# Output13-21.net
KiCad netlist of a schematic drawn in Altium Designer
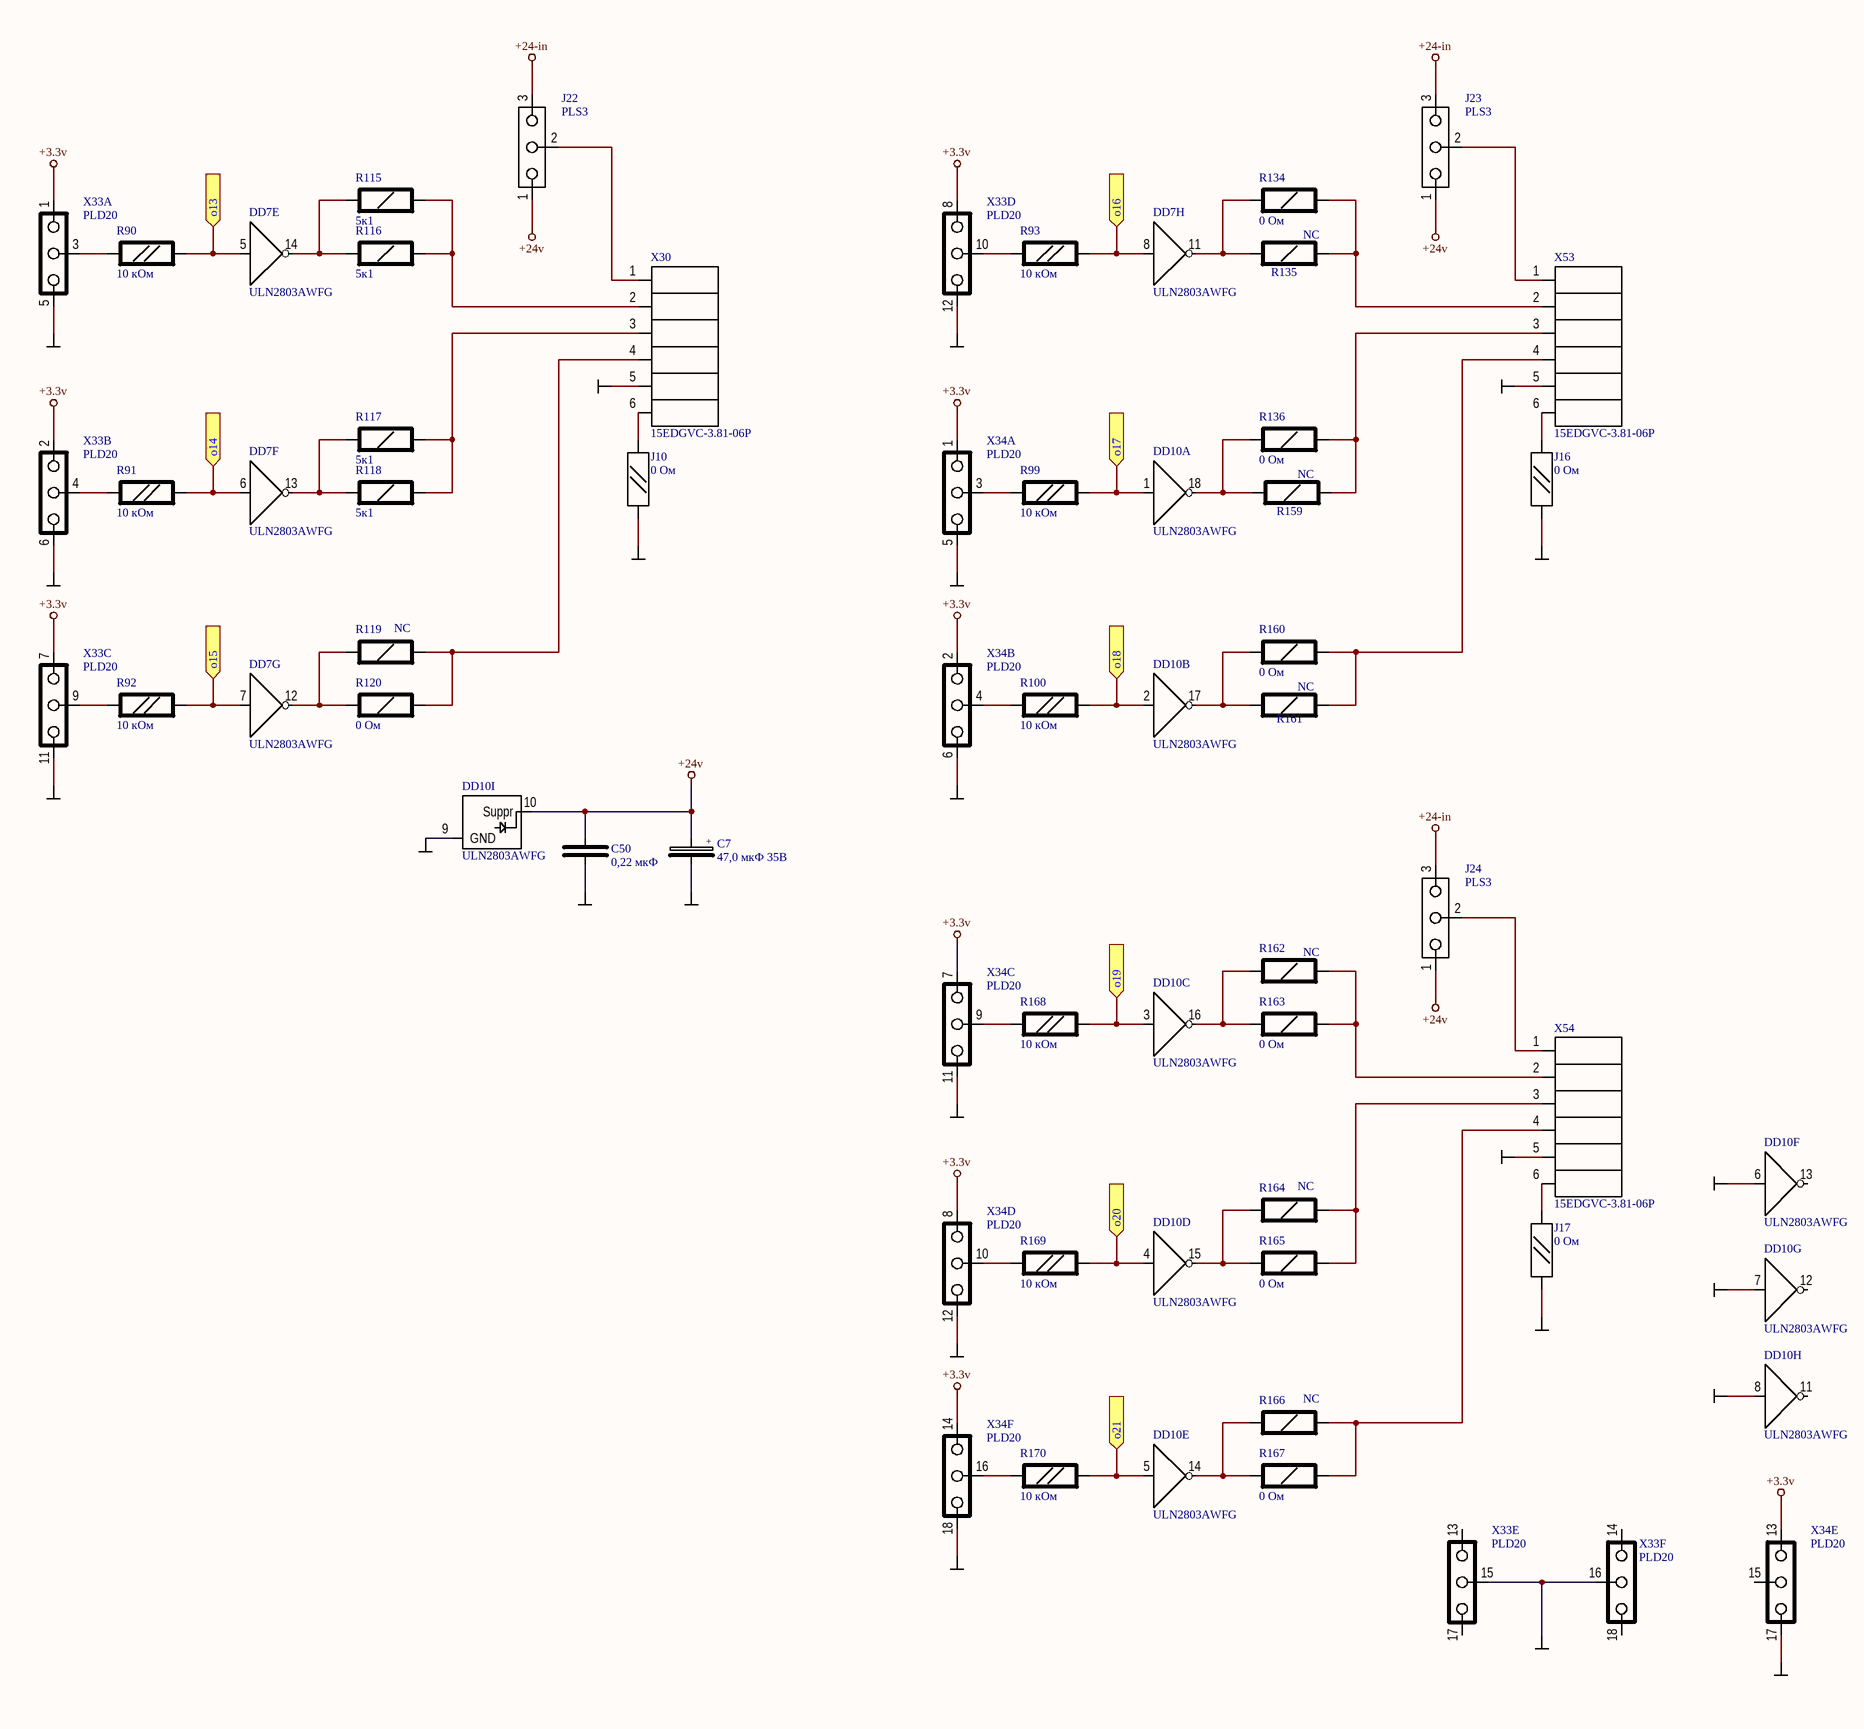
[diagram p0: Output13-21.SchDoc]

(export (version "E")
  (design (tool "Eeschema 10.0.6"))
  (components
    (comp (ref "C7")
      (value "47,0 мкФ 35В")
      (footprint "cap6")
      (description "5мм Электролитический конденсатор")
      (libsource (lib "SL02_22F") (part "C_e"))
    )
    (comp (ref "C50")
      (value "0,22 мкФ")
      (footprint "SMD0805CAP")
      (description "Чип конденсатор 0805")
      (fields (field (name "VOLTAGE") "50V"))
      (libsource (lib "SL02_22F") (part "C0805"))
    )
    (comp (ref "DD7")
      (value "ULN2803AWFG")
      (footprint "SOL18")
      (description "Буфер 8-канальный")
      (fields (field (name "VOLTAGE") "50V"))
      (libsource (lib "SL02_22F") (part "ULN2803"))
    )
    (comp (ref "DD10")
      (value "ULN2803AWFG")
      (footprint "SOL18")
      (description "Буфер 8-канальный")
      (fields (field (name "VOLTAGE") "50V"))
      (libsource (lib "SL02_22F") (part "ULN2803"))
    )
    (comp (ref "J10")
      (value "0 Ом")
      (footprint "SMD0805RES")
      (description "SMD 0805 перемычка")
      (libsource (lib "L02_22F") (part "JR0805"))
    )
    (comp (ref "J16")
      (value "0 Ом")
      (footprint "SMD0805RES")
      (description "SMD 0805 перемычка")
      (libsource (lib "L02_22F") (part "JR0805"))
    )
    (comp (ref "J17")
      (value "0 Ом")
      (footprint "SMD0805RES")
      (description "SMD 0805 перемычка")
      (libsource (lib "L02_22F") (part "JR0805"))
    )
    (comp (ref "J22")
      (value "PLS3")
      (footprint "HDR1X3")
      (description "Джампер PLS3 2.54мм")
      (libsource (lib "L02_22F") (part "PLS3"))
    )
    (comp (ref "J23")
      (value "PLS3")
      (footprint "HDR1X3")
      (description "Джампер PLS3 2.54мм")
      (libsource (lib "L02_22F") (part "PLS3"))
    )
    (comp (ref "J24")
      (value "PLS3")
      (footprint "HDR1X3")
      (description "Джампер PLS3 2.54мм")
      (libsource (lib "L02_22F") (part "PLS3"))
    )
    (comp (ref "R90")
      (value "10 кОм")
      (footprint "SMD0805RES")
      (description "Чип резистор 0805")
      (fields (field (name "TOLERANCE") "5%"))
      (libsource (lib "SL02_22F") (part "R0805"))
    )
    (comp (ref "R91")
      (value "10 кОм")
      (footprint "SMD0805RES")
      (description "Чип резистор 0805")
      (fields (field (name "TOLERANCE") "5%"))
      (libsource (lib "SL02_22F") (part "R0805"))
    )
    (comp (ref "R92")
      (value "10 кОм")
      (footprint "SMD0805RES")
      (description "Чип резистор 0805")
      (fields (field (name "TOLERANCE") "5%"))
      (libsource (lib "SL02_22F") (part "R0805"))
    )
    (comp (ref "R93")
      (value "10 кОм")
      (footprint "SMD0805RES")
      (description "Чип резистор 0805")
      (fields (field (name "TOLERANCE") "5%"))
      (libsource (lib "SL02_22F") (part "R0805"))
    )
    (comp (ref "R99")
      (value "10 кОм")
      (footprint "SMD0805RES")
      (description "Чип резистор 0805")
      (fields (field (name "TOLERANCE") "5%"))
      (libsource (lib "SL02_22F") (part "R0805"))
    )
    (comp (ref "R100")
      (value "10 кОм")
      (footprint "SMD0805RES")
      (description "Чип резистор 0805")
      (fields (field (name "TOLERANCE") "5%"))
      (libsource (lib "SL02_22F") (part "R0805"))
    )
    (comp (ref "R115")
      (value "5к1")
      (footprint "RES1206")
      (description "Чип резистор 1206")
      (fields (field (name "TOLERANCE") "5%"))
      (libsource (lib "SL02_22F") (part "R1206"))
    )
    (comp (ref "R116")
      (value "5к1")
      (footprint "RES1206")
      (description "Чип резистор 1206")
      (fields (field (name "TOLERANCE") "5%"))
      (libsource (lib "SL02_22F") (part "R1206"))
    )
    (comp (ref "R117")
      (value "5к1")
      (footprint "RES1206")
      (description "Чип резистор 1206")
      (fields (field (name "TOLERANCE") "5%"))
      (libsource (lib "SL02_22F") (part "R1206"))
    )
    (comp (ref "R118")
      (value "5к1")
      (footprint "RES1206")
      (description "Чип резистор 1206")
      (fields (field (name "TOLERANCE") "5%"))
      (libsource (lib "SL02_22F") (part "R1206"))
    )
    (comp (ref "R119")
      (value "~")
      (footprint "RES1206")
      (description "Чип резистор 1206")
      (fields (field (name "TOLERANCE") "5%") (field (name "SOLDEROPTON") "NC"))
      (libsource (lib "SL02_22F") (part "R1206"))
    )
    (comp (ref "R120")
      (value "0 Ом")
      (footprint "RES1206")
      (description "Чип резистор 1206")
      (fields (field (name "TOLERANCE") "5%"))
      (libsource (lib "SL02_22F") (part "R1206"))
    )
    (comp (ref "R134")
      (value "0 Ом")
      (footprint "RES1206")
      (description "Чип резистор 1206")
      (fields (field (name "TOLERANCE") "5%"))
      (libsource (lib "SL02_22F") (part "R1206"))
    )
    (comp (ref "R135")
      (value "~")
      (footprint "RES1206")
      (description "Чип резистор 1206")
      (fields (field (name "TOLERANCE") "5%") (field (name "SOLDEROPTON") "NC"))
      (libsource (lib "SL02_22F") (part "R1206"))
    )
    (comp (ref "R136")
      (value "0 Ом")
      (footprint "RES1206")
      (description "Чип резистор 1206")
      (fields (field (name "TOLERANCE") "5%"))
      (libsource (lib "SL02_22F") (part "R1206"))
    )
    (comp (ref "R159")
      (value "~")
      (footprint "RES1206")
      (description "Чип резистор 1206")
      (fields (field (name "TOLERANCE") "5%") (field (name "SOLDEROPTON") "NC"))
      (libsource (lib "SL02_22F") (part "R1206"))
    )
    (comp (ref "R160")
      (value "0 Ом")
      (footprint "RES1206")
      (description "Чип резистор 1206")
      (fields (field (name "TOLERANCE") "5%"))
      (libsource (lib "SL02_22F") (part "R1206"))
    )
    (comp (ref "R161")
      (value "~")
      (footprint "RES1206")
      (description "Чип резистор 1206")
      (fields (field (name "TOLERANCE") "5%") (field (name "SOLDEROPTON") "NC"))
      (libsource (lib "SL02_22F") (part "R1206"))
    )
    (comp (ref "R162")
      (value "~")
      (footprint "RES1206")
      (description "Чип резистор 1206")
      (fields (field (name "TOLERANCE") "5%") (field (name "SOLDEROPTON") "NC"))
      (libsource (lib "SL02_22F") (part "R1206"))
    )
    (comp (ref "R163")
      (value "0 Ом")
      (footprint "RES1206")
      (description "Чип резистор 1206")
      (fields (field (name "TOLERANCE") "5%"))
      (libsource (lib "SL02_22F") (part "R1206"))
    )
    (comp (ref "R164")
      (value "~")
      (footprint "RES1206")
      (description "Чип резистор 1206")
      (fields (field (name "TOLERANCE") "5%") (field (name "SOLDEROPTON") "NC"))
      (libsource (lib "SL02_22F") (part "R1206"))
    )
    (comp (ref "R165")
      (value "0 Ом")
      (footprint "RES1206")
      (description "Чип резистор 1206")
      (fields (field (name "TOLERANCE") "5%"))
      (libsource (lib "SL02_22F") (part "R1206"))
    )
    (comp (ref "R166")
      (value "~")
      (footprint "RES1206")
      (description "Чип резистор 1206")
      (fields (field (name "TOLERANCE") "5%") (field (name "SOLDEROPTON") "NC"))
      (libsource (lib "SL02_22F") (part "R1206"))
    )
    (comp (ref "R167")
      (value "0 Ом")
      (footprint "RES1206")
      (description "Чип резистор 1206")
      (fields (field (name "TOLERANCE") "5%"))
      (libsource (lib "SL02_22F") (part "R1206"))
    )
    (comp (ref "R168")
      (value "10 кОм")
      (footprint "SMD0805RES")
      (description "Чип резистор 0805")
      (fields (field (name "TOLERANCE") "5%"))
      (libsource (lib "SL02_22F") (part "R0805"))
    )
    (comp (ref "R169")
      (value "10 кОм")
      (footprint "SMD0805RES")
      (description "Чип резистор 0805")
      (fields (field (name "TOLERANCE") "5%"))
      (libsource (lib "SL02_22F") (part "R0805"))
    )
    (comp (ref "R170")
      (value "10 кОм")
      (footprint "SMD0805RES")
      (description "Чип резистор 0805")
      (fields (field (name "TOLERANCE") "5%"))
      (libsource (lib "SL02_22F") (part "R0805"))
    )
    (comp (ref "X30")
      (value "15EDGVC-3.81-06P")
      (footprint "15EDGVC_081_6")
      (description "Вилка  6/3.81")
      (fields (field (name "VOLTAGE") "2кВ"))
      (libsource (lib "L02_22F") (part "15EDGVC-3.81-06P"))
    )
    (comp (ref "X33")
      (value "PLD20")
      (footprint "pld2x10_1.27")
      (description "Вилка  PLD 20/1.27")
      (libsource (lib "") (part "PLD20_1"))
    )
    (comp (ref "X34")
      (value "PLD20")
      (footprint "pld2x10_1.27")
      (description "Вилка  PLD 20/1.27")
      (libsource (lib "SL02_22F") (part "PLD20"))
    )
    (comp (ref "X53")
      (value "15EDGVC-3.81-06P")
      (footprint "15EDGVC_081_6")
      (description "Вилка  6/3.81")
      (fields (field (name "VOLTAGE") "2кВ"))
      (libsource (lib "L02_22F") (part "15EDGVC-3.81-06P"))
    )
    (comp (ref "X54")
      (value "15EDGVC-3.81-06P")
      (footprint "15EDGVC_081_6")
      (description "Вилка  6/3.81")
      (fields (field (name "VOLTAGE") "2кВ"))
      (libsource (lib "L02_22F") (part "15EDGVC-3.81-06P"))
    )
  )
  (nets
    (net (code "1") (name "+3.3v") (class "Default")
      (node (ref "X33") (pin "1") (pinfunction "1_1") (pintype "passive"))
      (node (ref "X33") (pin "2") (pinfunction "2_2") (pintype "passive"))
      (node (ref "X33") (pin "7") (pinfunction "7_7") (pintype "passive"))
      (node (ref "X33") (pin "8") (pinfunction "8_8") (pintype "passive"))
      (node (ref "X34") (pin "1") (pinfunction "1_1") (pintype "passive"))
      (node (ref "X34") (pin "13") (pinfunction "13_13") (pintype "passive"))
      (node (ref "X34") (pin "14") (pinfunction "14_14") (pintype "passive"))
      (node (ref "X34") (pin "2") (pinfunction "2_2") (pintype "passive"))
      (node (ref "X34") (pin "7") (pinfunction "7_7") (pintype "passive"))
      (node (ref "X34") (pin "8") (pinfunction "8_8") (pintype "passive"))
    )
    (net (code "2") (name "+24-in") (class "Default")
      (node (ref "J22") (pin "3") (pinfunction "Left_3") (pintype "passive"))
      (node (ref "J23") (pin "3") (pinfunction "Left_3") (pintype "passive"))
      (node (ref "J24") (pin "3") (pinfunction "Left_3") (pintype "passive"))
    )
    (net (code "3") (name "+24v") (class "Default")
      (node (ref "C50") (pin "1") (pinfunction "1_1") (pintype "passive"))
      (node (ref "C7") (pin "1") (pinfunction "+_1") (pintype "passive"))
      (node (ref "DD10") (pin "10") (pinfunction "Suppr_10") (pintype "passive"))
      (node (ref "J22") (pin "1") (pinfunction "Right_1") (pintype "passive"))
      (node (ref "J23") (pin "1") (pinfunction "Right_1") (pintype "passive"))
      (node (ref "J24") (pin "1") (pinfunction "Right_1") (pintype "passive"))
    )
    (net (code "4") (name "/o13") (class "Default")
      (node (ref "DD7") (pin "5") (pinfunction "In_5") (pintype "input"))
      (node (ref "R90") (pin "1") (pinfunction "1_1") (pintype "passive"))
    )
    (net (code "5") (name "/o14") (class "Default")
      (node (ref "DD7") (pin "6") (pinfunction "In_6") (pintype "input"))
      (node (ref "R91") (pin "1") (pinfunction "1_1") (pintype "passive"))
    )
    (net (code "6") (name "/o15") (class "Default")
      (node (ref "DD7") (pin "7") (pinfunction "In_7") (pintype "input"))
      (node (ref "R92") (pin "1") (pinfunction "1_1") (pintype "passive"))
    )
    (net (code "7") (name "/o16") (class "Default")
      (node (ref "DD7") (pin "8") (pinfunction "In_8") (pintype "input"))
      (node (ref "R93") (pin "1") (pinfunction "1_1") (pintype "passive"))
    )
    (net (code "8") (name "/o17") (class "Default")
      (node (ref "DD10") (pin "1") (pinfunction "In_1") (pintype "input"))
      (node (ref "R99") (pin "1") (pinfunction "1_1") (pintype "passive"))
    )
    (net (code "9") (name "/o18") (class "Default")
      (node (ref "DD10") (pin "2") (pinfunction "In_2") (pintype "input"))
      (node (ref "R100") (pin "1") (pinfunction "1_1") (pintype "passive"))
    )
    (net (code "10") (name "/o19") (class "Default")
      (node (ref "DD10") (pin "3") (pinfunction "In_3") (pintype "input"))
      (node (ref "R168") (pin "1") (pinfunction "1_1") (pintype "passive"))
    )
    (net (code "11") (name "/o20") (class "Default")
      (node (ref "DD10") (pin "4") (pinfunction "In_4") (pintype "input"))
      (node (ref "R169") (pin "1") (pinfunction "1_1") (pintype "passive"))
    )
    (net (code "12") (name "/o21") (class "Default")
      (node (ref "DD10") (pin "5") (pinfunction "In_5") (pintype "input"))
      (node (ref "R170") (pin "1") (pinfunction "1_1") (pintype "passive"))
    )
    (net (code "13") (name "GND") (class "Default")
      (node (ref "C50") (pin "2") (pinfunction "2_2") (pintype "passive"))
      (node (ref "C7") (pin "2") (pinfunction "-_2") (pintype "passive"))
      (node (ref "DD10") (pin "6") (pinfunction "In_6") (pintype "input"))
      (node (ref "DD10") (pin "7") (pinfunction "In_7") (pintype "input"))
      (node (ref "DD10") (pin "8") (pinfunction "In_8") (pintype "input"))
      (node (ref "DD10") (pin "9") (pinfunction "GND_9") (pintype "passive"))
      (node (ref "J10") (pin "2") (pinfunction "2_2") (pintype "passive"))
      (node (ref "J16") (pin "2") (pinfunction "2_2") (pintype "passive"))
      (node (ref "J17") (pin "2") (pinfunction "2_2") (pintype "passive"))
      (node (ref "X30") (pin "5") (pinfunction "5_5") (pintype "passive"))
      (node (ref "X33") (pin "11") (pinfunction "11_11") (pintype "passive"))
      (node (ref "X33") (pin "12") (pinfunction "12_12") (pintype "passive"))
      (node (ref "X33") (pin "15") (pinfunction "15_15") (pintype "passive"))
      (node (ref "X33") (pin "16") (pinfunction "16_16") (pintype "passive"))
      (node (ref "X33") (pin "5") (pinfunction "5_5") (pintype "passive"))
      (node (ref "X33") (pin "6") (pinfunction "6_6") (pintype "passive"))
      (node (ref "X34") (pin "11") (pinfunction "11_11") (pintype "passive"))
      (node (ref "X34") (pin "12") (pinfunction "12_12") (pintype "passive"))
      (node (ref "X34") (pin "17") (pinfunction "17_17") (pintype "passive"))
      (node (ref "X34") (pin "18") (pinfunction "18_18") (pintype "passive"))
      (node (ref "X34") (pin "5") (pinfunction "5_5") (pintype "passive"))
      (node (ref "X34") (pin "6") (pinfunction "6_6") (pintype "passive"))
      (node (ref "X53") (pin "5") (pinfunction "5_5") (pintype "passive"))
      (node (ref "X54") (pin "5") (pinfunction "5_5") (pintype "passive"))
    )
    (net (code "14") (name "Net-(DD7E-OUT)") (class "Default")
      (node (ref "DD7") (pin "14") (pinfunction "OUT_14") (pintype "output"))
      (node (ref "R115") (pin "2") (pinfunction "2_2") (pintype "passive"))
      (node (ref "R116") (pin "2") (pinfunction "2_2") (pintype "passive"))
    )
    (net (code "15") (name "Net-(DD7F-OUT)") (class "Default")
      (node (ref "DD7") (pin "13") (pinfunction "OUT_13") (pintype "output"))
      (node (ref "R117") (pin "2") (pinfunction "2_2") (pintype "passive"))
      (node (ref "R118") (pin "2") (pinfunction "2_2") (pintype "passive"))
    )
    (net (code "16") (name "Net-(DD7G-OUT)") (class "Default")
      (node (ref "DD7") (pin "12") (pinfunction "OUT_12") (pintype "output"))
      (node (ref "R119") (pin "2") (pinfunction "2_2") (pintype "passive"))
      (node (ref "R120") (pin "2") (pinfunction "2_2") (pintype "passive"))
    )
    (net (code "17") (name "Net-(DD7H-OUT)") (class "Default")
      (node (ref "DD7") (pin "11") (pinfunction "OUT_11") (pintype "output"))
      (node (ref "R134") (pin "2") (pinfunction "2_2") (pintype "passive"))
      (node (ref "R135") (pin "2") (pinfunction "2_2") (pintype "passive"))
    )
    (net (code "18") (name "Net-(DD10A-OUT)") (class "Default")
      (node (ref "DD10") (pin "18") (pinfunction "OUT_18") (pintype "output"))
      (node (ref "R136") (pin "2") (pinfunction "2_2") (pintype "passive"))
      (node (ref "R159") (pin "2") (pinfunction "2_2") (pintype "passive"))
    )
    (net (code "19") (name "Net-(DD10B-OUT)") (class "Default")
      (node (ref "DD10") (pin "17") (pinfunction "OUT_17") (pintype "output"))
      (node (ref "R160") (pin "2") (pinfunction "2_2") (pintype "passive"))
      (node (ref "R161") (pin "2") (pinfunction "2_2") (pintype "passive"))
    )
    (net (code "20") (name "Net-(DD10C-OUT)") (class "Default")
      (node (ref "DD10") (pin "16") (pinfunction "OUT_16") (pintype "output"))
      (node (ref "R162") (pin "2") (pinfunction "2_2") (pintype "passive"))
      (node (ref "R163") (pin "2") (pinfunction "2_2") (pintype "passive"))
    )
    (net (code "21") (name "Net-(DD10D-OUT)") (class "Default")
      (node (ref "DD10") (pin "15") (pinfunction "OUT_15") (pintype "output"))
      (node (ref "R164") (pin "2") (pinfunction "2_2") (pintype "passive"))
      (node (ref "R165") (pin "2") (pinfunction "2_2") (pintype "passive"))
    )
    (net (code "22") (name "Net-(DD10E-OUT)") (class "Default")
      (node (ref "DD10") (pin "14") (pinfunction "OUT_14") (pintype "output"))
      (node (ref "R166") (pin "2") (pinfunction "2_2") (pintype "passive"))
      (node (ref "R167") (pin "2") (pinfunction "2_2") (pintype "passive"))
    )
    (net (code "23") (name "Net-(J10-Pad1)") (class "Default")
      (node (ref "J10") (pin "1") (pinfunction "1_1") (pintype "passive"))
      (node (ref "X30") (pin "6") (pinfunction "6_6") (pintype "passive"))
    )
    (net (code "24") (name "Net-(J16-Pad1)") (class "Default")
      (node (ref "J16") (pin "1") (pinfunction "1_1") (pintype "passive"))
      (node (ref "X53") (pin "6") (pinfunction "6_6") (pintype "passive"))
    )
    (net (code "25") (name "Net-(J17-Pad1)") (class "Default")
      (node (ref "J17") (pin "1") (pinfunction "1_1") (pintype "passive"))
      (node (ref "X54") (pin "6") (pinfunction "6_6") (pintype "passive"))
    )
    (net (code "26") (name "Net-(J22-Cetnter)") (class "Default")
      (node (ref "J22") (pin "2") (pinfunction "Cetnter_2") (pintype "passive"))
      (node (ref "X30") (pin "1") (pinfunction "1_1") (pintype "passive"))
    )
    (net (code "27") (name "Net-(J23-Cetnter)") (class "Default")
      (node (ref "J23") (pin "2") (pinfunction "Cetnter_2") (pintype "passive"))
      (node (ref "X53") (pin "1") (pinfunction "1_1") (pintype "passive"))
    )
    (net (code "28") (name "Net-(J24-Cetnter)") (class "Default")
      (node (ref "J24") (pin "2") (pinfunction "Cetnter_2") (pintype "passive"))
      (node (ref "X54") (pin "1") (pinfunction "1_1") (pintype "passive"))
    )
    (net (code "29") (name "Net-(R90-Pad2)") (class "Default")
      (node (ref "R90") (pin "2") (pinfunction "2_2") (pintype "passive"))
      (node (ref "X33") (pin "3") (pinfunction "3_3") (pintype "passive"))
    )
    (net (code "30") (name "Net-(R91-Pad2)") (class "Default")
      (node (ref "R91") (pin "2") (pinfunction "2_2") (pintype "passive"))
      (node (ref "X33") (pin "4") (pinfunction "4_4") (pintype "passive"))
    )
    (net (code "31") (name "Net-(R92-Pad2)") (class "Default")
      (node (ref "R92") (pin "2") (pinfunction "2_2") (pintype "passive"))
      (node (ref "X33") (pin "9") (pinfunction "9_9") (pintype "passive"))
    )
    (net (code "32") (name "Net-(R93-Pad2)") (class "Default")
      (node (ref "R93") (pin "2") (pinfunction "2_2") (pintype "passive"))
      (node (ref "X33") (pin "10") (pinfunction "10_10") (pintype "passive"))
    )
    (net (code "33") (name "Net-(R99-Pad2)") (class "Default")
      (node (ref "R99") (pin "2") (pinfunction "2_2") (pintype "passive"))
      (node (ref "X34") (pin "3") (pinfunction "3_3") (pintype "passive"))
    )
    (net (code "34") (name "Net-(R100-Pad2)") (class "Default")
      (node (ref "R100") (pin "2") (pinfunction "2_2") (pintype "passive"))
      (node (ref "X34") (pin "4") (pinfunction "4_4") (pintype "passive"))
    )
    (net (code "35") (name "Net-(R115-Pad1)") (class "Default")
      (node (ref "R115") (pin "1") (pinfunction "1_1") (pintype "passive"))
      (node (ref "R116") (pin "1") (pinfunction "1_1") (pintype "passive"))
      (node (ref "X30") (pin "2") (pinfunction "2_2") (pintype "passive"))
    )
    (net (code "36") (name "Net-(R117-Pad1)") (class "Default")
      (node (ref "R117") (pin "1") (pinfunction "1_1") (pintype "passive"))
      (node (ref "R118") (pin "1") (pinfunction "1_1") (pintype "passive"))
      (node (ref "X30") (pin "3") (pinfunction "3_3") (pintype "passive"))
    )
    (net (code "37") (name "Net-(R119-Pad1)") (class "Default")
      (node (ref "R119") (pin "1") (pinfunction "1_1") (pintype "passive"))
      (node (ref "R120") (pin "1") (pinfunction "1_1") (pintype "passive"))
      (node (ref "X30") (pin "4") (pinfunction "4_4") (pintype "passive"))
    )
    (net (code "38") (name "Net-(R134-Pad1)") (class "Default")
      (node (ref "R134") (pin "1") (pinfunction "1_1") (pintype "passive"))
      (node (ref "R135") (pin "1") (pinfunction "1_1") (pintype "passive"))
      (node (ref "X53") (pin "2") (pinfunction "2_2") (pintype "passive"))
    )
    (net (code "39") (name "Net-(R136-Pad1)") (class "Default")
      (node (ref "R136") (pin "1") (pinfunction "1_1") (pintype "passive"))
      (node (ref "R159") (pin "1") (pinfunction "1_1") (pintype "passive"))
      (node (ref "X53") (pin "3") (pinfunction "3_3") (pintype "passive"))
    )
    (net (code "40") (name "Net-(R160-Pad1)") (class "Default")
      (node (ref "R160") (pin "1") (pinfunction "1_1") (pintype "passive"))
      (node (ref "R161") (pin "1") (pinfunction "1_1") (pintype "passive"))
      (node (ref "X53") (pin "4") (pinfunction "4_4") (pintype "passive"))
    )
    (net (code "41") (name "Net-(R162-Pad1)") (class "Default")
      (node (ref "R162") (pin "1") (pinfunction "1_1") (pintype "passive"))
      (node (ref "R163") (pin "1") (pinfunction "1_1") (pintype "passive"))
      (node (ref "X54") (pin "2") (pinfunction "2_2") (pintype "passive"))
    )
    (net (code "42") (name "Net-(R164-Pad1)") (class "Default")
      (node (ref "R164") (pin "1") (pinfunction "1_1") (pintype "passive"))
      (node (ref "R165") (pin "1") (pinfunction "1_1") (pintype "passive"))
      (node (ref "X54") (pin "3") (pinfunction "3_3") (pintype "passive"))
    )
    (net (code "43") (name "Net-(R166-Pad1)") (class "Default")
      (node (ref "R166") (pin "1") (pinfunction "1_1") (pintype "passive"))
      (node (ref "R167") (pin "1") (pinfunction "1_1") (pintype "passive"))
      (node (ref "X54") (pin "4") (pinfunction "4_4") (pintype "passive"))
    )
    (net (code "44") (name "Net-(R168-Pad2)") (class "Default")
      (node (ref "R168") (pin "2") (pinfunction "2_2") (pintype "passive"))
      (node (ref "X34") (pin "9") (pinfunction "9_9") (pintype "passive"))
    )
    (net (code "45") (name "Net-(R169-Pad2)") (class "Default")
      (node (ref "R169") (pin "2") (pinfunction "2_2") (pintype "passive"))
      (node (ref "X34") (pin "10") (pinfunction "10_10") (pintype "passive"))
    )
    (net (code "46") (name "Net-(R170-Pad2)") (class "Default")
      (node (ref "R170") (pin "2") (pinfunction "2_2") (pintype "passive"))
      (node (ref "X34") (pin "16") (pinfunction "16_16") (pintype "passive"))
    )
    (net (code "47") (name "unconnected-(DD10F-OUT-Pad13)") (class "Default")
      (node (ref "DD10") (pin "13") (pinfunction "OUT_13") (pintype "output"))
    )
    (net (code "48") (name "unconnected-(DD10G-OUT-Pad12)") (class "Default")
      (node (ref "DD10") (pin "12") (pinfunction "OUT_12") (pintype "output"))
    )
    (net (code "49") (name "unconnected-(DD10H-OUT-Pad11)") (class "Default")
      (node (ref "DD10") (pin "11") (pinfunction "OUT_11") (pintype "output"))
    )
    (net (code "50") (name "unconnected-(X33-Pad13)") (class "Default")
      (node (ref "X33") (pin "13") (pinfunction "13_13") (pintype "passive"))
    )
    (net (code "51") (name "unconnected-(X33-Pad14)") (class "Default")
      (node (ref "X33") (pin "14") (pinfunction "14_14") (pintype "passive"))
    )
    (net (code "52") (name "unconnected-(X33-Pad17)") (class "Default")
      (node (ref "X33") (pin "17") (pinfunction "17_17") (pintype "passive"))
    )
    (net (code "53") (name "unconnected-(X33-Pad18)") (class "Default")
      (node (ref "X33") (pin "18") (pinfunction "18_18") (pintype "passive"))
    )
    (net (code "54") (name "unconnected-(X34-Pad15)") (class "Default")
      (node (ref "X34") (pin "15") (pinfunction "15_15") (pintype "passive"))
    )
  )
)
